# link_b.net
KiCad netlist of a schematic drawn in Altium Designer
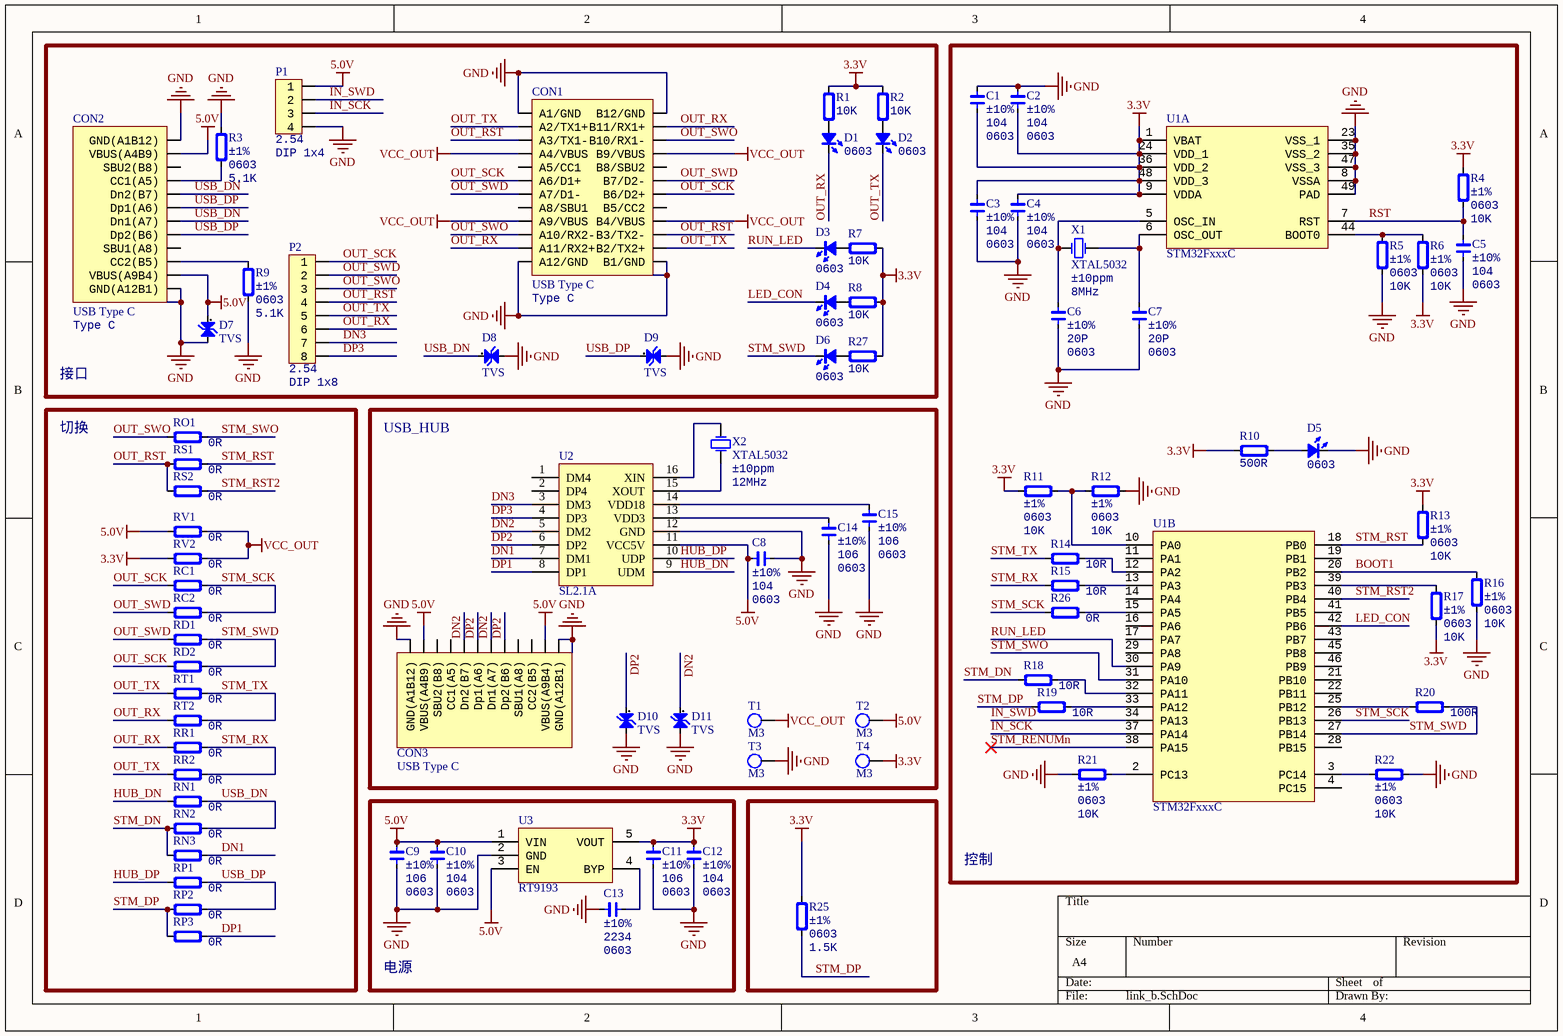
[diagram p0: link_b.SchDoc]

(export (version "E")
  (design (tool "Eeschema 10.0.6"))
  (components
    (comp (ref "C1")
      (value "104")
      (footprint "CAP_0603")
      (description "Capacitor")
      (fields (field (name "NOTE") "±10%") (field (name "TYPE") "0603") (field (name "Comment") "C0603"))
      (libsource (lib "Integrated_Library") (part "Cap_0603"))
    )
    (comp (ref "C2")
      (value "104")
      (footprint "CAP_0603")
      (description "Capacitor")
      (fields (field (name "NOTE") "±10%") (field (name "TYPE") "0603") (field (name "Comment") "C0603"))
      (libsource (lib "Integrated_Library") (part "Cap_0603"))
    )
    (comp (ref "C3")
      (value "104")
      (footprint "CAP_0603")
      (description "Capacitor")
      (fields (field (name "NOTE") "±10%") (field (name "TYPE") "0603") (field (name "Comment") "C0603"))
      (libsource (lib "Integrated_Library") (part "Cap_0603"))
    )
    (comp (ref "C4")
      (value "104")
      (footprint "CAP_0603")
      (description "Capacitor")
      (fields (field (name "NOTE") "±10%") (field (name "TYPE") "0603") (field (name "Comment") "C0603"))
      (libsource (lib "Integrated_Library") (part "Cap_0603"))
    )
    (comp (ref "C5")
      (value "104")
      (footprint "CAP_0603")
      (description "Capacitor")
      (fields (field (name "NOTE") "±10%") (field (name "TYPE") "0603") (field (name "Comment") "C0603"))
      (libsource (lib "Integrated_Library") (part "Cap_0603"))
    )
    (comp (ref "C6")
      (value "20P")
      (footprint "CAP_0603")
      (description "Capacitor")
      (fields (field (name "NOTE") "±10%") (field (name "TYPE") "0603") (field (name "Comment") "C0603"))
      (libsource (lib "Integrated_Library") (part "Cap_0603"))
    )
    (comp (ref "C7")
      (value "20P")
      (footprint "CAP_0603")
      (description "Capacitor")
      (fields (field (name "NOTE") "±10%") (field (name "TYPE") "0603") (field (name "Comment") "C0603"))
      (libsource (lib "Integrated_Library") (part "Cap_0603"))
    )
    (comp (ref "C8")
      (value "104")
      (footprint "CAP_0603")
      (description "Capacitor")
      (fields (field (name "NOTE") "±10%") (field (name "TYPE") "0603") (field (name "Comment") "C0603"))
      (libsource (lib "") (part "Cap_0603_3"))
    )
    (comp (ref "C9")
      (value "106")
      (footprint "CAP_0603")
      (description "Capacitor")
      (fields (field (name "NOTE") "±10%") (field (name "TYPE") "0603") (field (name "Comment") "C0603"))
      (libsource (lib "Integrated_Library") (part "Cap_0603"))
    )
    (comp (ref "C10")
      (value "104")
      (footprint "CAP_0603")
      (description "Capacitor")
      (fields (field (name "NOTE") "±10%") (field (name "TYPE") "0603") (field (name "Comment") "C0603"))
      (libsource (lib "Integrated_Library") (part "Cap_0603"))
    )
    (comp (ref "C11")
      (value "106")
      (footprint "CAP_0603")
      (description "Capacitor")
      (fields (field (name "NOTE") "±10%") (field (name "TYPE") "0603") (field (name "Comment") "C0603"))
      (libsource (lib "Integrated_Library") (part "Cap_0603"))
    )
    (comp (ref "C12")
      (value "104")
      (footprint "CAP_0603")
      (description "Capacitor")
      (fields (field (name "NOTE") "±10%") (field (name "TYPE") "0603") (field (name "Comment") "C0603"))
      (libsource (lib "Integrated_Library") (part "Cap_0603"))
    )
    (comp (ref "C13")
      (value "2234")
      (footprint "CAP_0603")
      (description "Capacitor")
      (fields (field (name "NOTE") "±10%") (field (name "TYPE") "0603") (field (name "Comment") "C0603"))
      (libsource (lib "") (part "Cap_0603_1"))
    )
    (comp (ref "C14")
      (value "106")
      (footprint "CAP_0603")
      (description "Capacitor")
      (fields (field (name "NOTE") "±10%") (field (name "TYPE") "0603") (field (name "Comment") "C0603"))
      (libsource (lib "") (part "Cap_0603_2"))
    )
    (comp (ref "C15")
      (value "106")
      (footprint "CAP_0603")
      (description "Capacitor")
      (fields (field (name "NOTE") "±10%") (field (name "TYPE") "0603") (field (name "Comment") "C0603"))
      (libsource (lib "") (part "Cap_0603_2"))
    )
    (comp (ref "CON1")
      (value "USB Type C")
      (footprint "USB_TypeC_SMD_24P")
      (description "USB")
      (fields (field (name "ALTIUM_VALUE") "Type C"))
      (libsource (lib "Integrated_Library") (part "USB_TypeC"))
    )
    (comp (ref "CON2")
      (value "USB Type C")
      (footprint "USB_TypeC_SMD_16P")
      (description "USB")
      (fields (field (name "ALTIUM_VALUE") "Type C"))
      (libsource (lib "") (part "USB_TypeC_16P_1"))
    )
    (comp (ref "CON3")
      (value "USB Type C")
      (footprint "USB_TypeC_SMD_16P")
      (description "USB")
      (libsource (lib "Integrated_Library") (part "USB_TypeC_16P"))
    )
    (comp (ref "D1")
      (value "D0603")
      (footprint "LED_0603_RED")
      (description "LED")
      (fields (field (name "TYPE") "0603"))
      (libsource (lib "") (part "LED_0603_1"))
    )
    (comp (ref "D2")
      (value "D0603")
      (footprint "LED_0603_RED")
      (description "LED")
      (fields (field (name "TYPE") "0603"))
      (libsource (lib "") (part "LED_0603_1"))
    )
    (comp (ref "D3")
      (value "D0603")
      (footprint "LED_0603_RED")
      (description "LED")
      (fields (field (name "TYPE") "0603"))
      (libsource (lib "Integrated_Library") (part "LED_0603"))
    )
    (comp (ref "D4")
      (value "D0603")
      (footprint "LED_0603_RED")
      (description "LED")
      (fields (field (name "TYPE") "0603"))
      (libsource (lib "Integrated_Library") (part "LED_0603"))
    )
    (comp (ref "D5")
      (value "D0603")
      (footprint "LED_0603_RED")
      (description "LED")
      (fields (field (name "TYPE") "0603"))
      (libsource (lib "") (part "LED_0603_2"))
    )
    (comp (ref "D6")
      (value "D0603")
      (footprint "LED_0603_RED")
      (description "LED")
      (fields (field (name "TYPE") "0603"))
      (libsource (lib "Integrated_Library") (part "LED_0603"))
    )
    (comp (ref "D7")
      (value "TVS")
      (footprint "LED_0603_YELLOW")
      (description "静电保护二极管,VRWM=5V.IPP=9.4A")
      (libsource (lib "MxM_Library") (part "ESD LESD5D5.0CT1G"))
    )
    (comp (ref "D8")
      (value "TVS")
      (footprint "LED_0603_YELLOW")
      (description "静电保护二极管,VRWM=5V.IPP=9.4A")
      (libsource (lib "MxM_Library") (part "ESD LESD5D5.0CT1G"))
    )
    (comp (ref "D9")
      (value "TVS")
      (footprint "LED_0603_YELLOW")
      (description "静电保护二极管,VRWM=5V.IPP=9.4A")
      (libsource (lib "MxM_Library") (part "ESD LESD5D5.0CT1G"))
    )
    (comp (ref "D10")
      (value "TVS")
      (footprint "LED_0603_YELLOW")
      (description "静电保护二极管,VRWM=5V.IPP=9.4A")
      (libsource (lib "MxM_Library") (part "ESD LESD5D5.0CT1G"))
    )
    (comp (ref "D11")
      (value "TVS")
      (footprint "LED_0603_YELLOW")
      (description "静电保护二极管,VRWM=5V.IPP=9.4A")
      (libsource (lib "MxM_Library") (part "ESD LESD5D5.0CT1G"))
    )
    (comp (ref "P1")
      (value "2.54")
      (footprint "HDR1x4_TOP")
      (description "Header Top")
      (fields (field (name "TYPE") "DIP 1x4") (field (name "Comment") "HDR1x4"))
      (libsource (lib "Integrated_Library") (part "HDR1x4_2.54TOP"))
    )
    (comp (ref "P2")
      (value "2.54")
      (footprint "HDR1x8_TOP")
      (description "Header Top")
      (fields (field (name "TYPE") "DIP 1x8") (field (name "Comment") "HDR1x8"))
      (libsource (lib "Integrated_Library") (part "HDR1x8_2.54TOP"))
    )
    (comp (ref "R1")
      (value "10K")
      (footprint "RES_0603")
      (description "Resistor")
      (fields (field (name "Comment") "R0603"))
      (libsource (lib "Integrated_Library") (part "Res_0603"))
    )
    (comp (ref "R2")
      (value "10K")
      (footprint "RES_0603")
      (description "Resistor")
      (fields (field (name "Comment") "R0603"))
      (libsource (lib "Integrated_Library") (part "Res_0603"))
    )
    (comp (ref "R3")
      (value "5.1K")
      (footprint "RES_0603")
      (description "Resistor")
      (fields (field (name "NOTE") "±1%") (field (name "TYPE") "0603") (field (name "Comment") "R0603"))
      (libsource (lib "Integrated_Library") (part "Res_0603"))
    )
    (comp (ref "R4")
      (value "10K")
      (footprint "RES_0603")
      (description "Resistor")
      (fields (field (name "NOTE") "±1%") (field (name "TYPE") "0603") (field (name "Comment") "R0603"))
      (libsource (lib "Integrated_Library") (part "Res_0603"))
    )
    (comp (ref "R5")
      (value "10K")
      (footprint "RES_0603")
      (description "Resistor")
      (fields (field (name "NOTE") "±1%") (field (name "TYPE") "0603") (field (name "Comment") "R0603"))
      (libsource (lib "Integrated_Library") (part "Res_0603"))
    )
    (comp (ref "R6")
      (value "10K")
      (footprint "RES_0603")
      (description "Resistor")
      (fields (field (name "NOTE") "±1%") (field (name "TYPE") "0603") (field (name "Comment") "R0603"))
      (libsource (lib "Integrated_Library") (part "Res_0603"))
    )
    (comp (ref "R7")
      (value "10K")
      (footprint "RES_0603")
      (description "Resistor")
      (fields (field (name "Comment") "R0603"))
      (libsource (lib "Integrated_Library") (part "Res_0603"))
    )
    (comp (ref "R8")
      (value "10K")
      (footprint "RES_0603")
      (description "Resistor")
      (fields (field (name "Comment") "R0603"))
      (libsource (lib "Integrated_Library") (part "Res_0603"))
    )
    (comp (ref "R9")
      (value "5.1K")
      (footprint "RES_0603")
      (description "Resistor")
      (fields (field (name "NOTE") "±1%") (field (name "TYPE") "0603") (field (name "Comment") "R0603"))
      (libsource (lib "Integrated_Library") (part "Res_0603"))
    )
    (comp (ref "R10")
      (value "500R")
      (footprint "RES_0603")
      (description "Resistor")
      (fields (field (name "Comment") "R0603"))
      (libsource (lib "Integrated_Library") (part "Res_0603"))
    )
    (comp (ref "R11")
      (value "10K")
      (footprint "RES_0603")
      (description "Resistor")
      (fields (field (name "NOTE") "±1%") (field (name "TYPE") "0603") (field (name "Comment") "R0603"))
      (libsource (lib "Integrated_Library") (part "Res_0603"))
    )
    (comp (ref "R12")
      (value "10K")
      (footprint "RES_0603")
      (description "Resistor")
      (fields (field (name "NOTE") "±1%") (field (name "TYPE") "0603") (field (name "Comment") "R0603"))
      (libsource (lib "Integrated_Library") (part "Res_0603"))
    )
    (comp (ref "R13")
      (value "10K")
      (footprint "RES_0603")
      (description "Resistor")
      (fields (field (name "NOTE") "±1%") (field (name "TYPE") "0603") (field (name "Comment") "R0603"))
      (libsource (lib "Integrated_Library") (part "Res_0603"))
    )
    (comp (ref "R14")
      (value "10R")
      (footprint "RES_0603")
      (description "Resistor")
      (fields (field (name "Comment") "R0603"))
      (libsource (lib "Integrated_Library") (part "Res_0603"))
    )
    (comp (ref "R15")
      (value "10R")
      (footprint "RES_0603")
      (description "Resistor")
      (fields (field (name "Comment") "R0603"))
      (libsource (lib "Integrated_Library") (part "Res_0603"))
    )
    (comp (ref "R16")
      (value "10K")
      (footprint "RES_0603")
      (description "Resistor")
      (fields (field (name "NOTE") "±1%") (field (name "TYPE") "0603") (field (name "Comment") "R0603"))
      (libsource (lib "Integrated_Library") (part "Res_0603"))
    )
    (comp (ref "R17")
      (value "10K")
      (footprint "RES_0603")
      (description "Resistor")
      (fields (field (name "NOTE") "±1%") (field (name "TYPE") "0603") (field (name "Comment") "R0603"))
      (libsource (lib "Integrated_Library") (part "Res_0603"))
    )
    (comp (ref "R18")
      (value "10R")
      (footprint "RES_0603")
      (description "Resistor")
      (fields (field (name "Comment") "R0603"))
      (libsource (lib "Integrated_Library") (part "Res_0603"))
    )
    (comp (ref "R19")
      (value "10R")
      (footprint "RES_0603")
      (description "Resistor")
      (fields (field (name "Comment") "R0603"))
      (libsource (lib "Integrated_Library") (part "Res_0603"))
    )
    (comp (ref "R20")
      (value "100R")
      (footprint "RES_0603")
      (description "Resistor")
      (fields (field (name "Comment") "R0603"))
      (libsource (lib "Integrated_Library") (part "Res_0603"))
    )
    (comp (ref "R21")
      (value "10K")
      (footprint "RES_0603")
      (description "Resistor")
      (fields (field (name "NOTE") "±1%") (field (name "TYPE") "0603") (field (name "Comment") "R0603"))
      (libsource (lib "Integrated_Library") (part "Res_0603"))
    )
    (comp (ref "R22")
      (value "10K")
      (footprint "RES_0603")
      (description "Resistor")
      (fields (field (name "NOTE") "±1%") (field (name "TYPE") "0603") (field (name "Comment") "R0603"))
      (libsource (lib "Integrated_Library") (part "Res_0603"))
    )
    (comp (ref "R25")
      (value "1.5K")
      (footprint "RES_0603")
      (description "Resistor")
      (fields (field (name "NOTE") "±1%") (field (name "TYPE") "0603") (field (name "Comment") "R0603"))
      (libsource (lib "Integrated_Library") (part "Res_0603"))
    )
    (comp (ref "R26")
      (value "0R")
      (footprint "RES_0603")
      (description "Resistor")
      (fields (field (name "Comment") "R0603"))
      (libsource (lib "Integrated_Library") (part "Res_0603"))
    )
    (comp (ref "R27")
      (value "10K")
      (footprint "RES_0603")
      (description "Resistor")
      (fields (field (name "Comment") "R0603"))
      (libsource (lib "Integrated_Library") (part "Res_0603"))
    )
    (comp (ref "RC1")
      (value "0R")
      (footprint "RES_0603")
      (description "Resistor")
      (fields (field (name "Comment") "R0603"))
      (libsource (lib "Integrated_Library") (part "Res_0603"))
    )
    (comp (ref "RC2")
      (value "0R")
      (footprint "RES_0603")
      (description "Resistor")
      (fields (field (name "Comment") "R0603"))
      (libsource (lib "Integrated_Library") (part "Res_0603"))
    )
    (comp (ref "RD1")
      (value "0R")
      (footprint "RES_0603")
      (description "Resistor")
      (fields (field (name "Comment") "R0603"))
      (libsource (lib "Integrated_Library") (part "Res_0603"))
    )
    (comp (ref "RD2")
      (value "0R")
      (footprint "RES_0603")
      (description "Resistor")
      (fields (field (name "Comment") "R0603"))
      (libsource (lib "Integrated_Library") (part "Res_0603"))
    )
    (comp (ref "RN1")
      (value "0R")
      (footprint "RES_0603")
      (description "Resistor")
      (fields (field (name "Comment") "R0603"))
      (libsource (lib "Integrated_Library") (part "Res_0603"))
    )
    (comp (ref "RN2")
      (value "0R")
      (footprint "RES_0603")
      (description "Resistor")
      (fields (field (name "Comment") "R0603"))
      (libsource (lib "Integrated_Library") (part "Res_0603"))
    )
    (comp (ref "RN3")
      (value "0R")
      (footprint "RES_0603")
      (description "Resistor")
      (fields (field (name "Comment") "R0603"))
      (libsource (lib "Integrated_Library") (part "Res_0603"))
    )
    (comp (ref "RO1")
      (value "0R")
      (footprint "RES_0603")
      (description "Resistor")
      (fields (field (name "Comment") "R0603"))
      (libsource (lib "Integrated_Library") (part "Res_0603"))
    )
    (comp (ref "RP1")
      (value "0R")
      (footprint "RES_0603")
      (description "Resistor")
      (fields (field (name "Comment") "R0603"))
      (libsource (lib "Integrated_Library") (part "Res_0603"))
    )
    (comp (ref "RP2")
      (value "0R")
      (footprint "RES_0603")
      (description "Resistor")
      (fields (field (name "Comment") "R0603"))
      (libsource (lib "Integrated_Library") (part "Res_0603"))
    )
    (comp (ref "RP3")
      (value "0R")
      (footprint "RES_0603")
      (description "Resistor")
      (fields (field (name "Comment") "R0603"))
      (libsource (lib "Integrated_Library") (part "Res_0603"))
    )
    (comp (ref "RR1")
      (value "0R")
      (footprint "RES_0603")
      (description "Resistor")
      (fields (field (name "Comment") "R0603"))
      (libsource (lib "Integrated_Library") (part "Res_0603"))
    )
    (comp (ref "RR2")
      (value "0R")
      (footprint "RES_0603")
      (description "Resistor")
      (fields (field (name "Comment") "R0603"))
      (libsource (lib "Integrated_Library") (part "Res_0603"))
    )
    (comp (ref "RS1")
      (value "0R")
      (footprint "RES_0603")
      (description "Resistor")
      (fields (field (name "Comment") "R0603"))
      (libsource (lib "Integrated_Library") (part "Res_0603"))
    )
    (comp (ref "RS2")
      (value "0R")
      (footprint "RES_0603")
      (description "Resistor")
      (fields (field (name "Comment") "R0603"))
      (libsource (lib "Integrated_Library") (part "Res_0603"))
    )
    (comp (ref "RT1")
      (value "0R")
      (footprint "RES_0603")
      (description "Resistor")
      (fields (field (name "Comment") "R0603"))
      (libsource (lib "Integrated_Library") (part "Res_0603"))
    )
    (comp (ref "RT2")
      (value "0R")
      (footprint "RES_0603")
      (description "Resistor")
      (fields (field (name "Comment") "R0603"))
      (libsource (lib "Integrated_Library") (part "Res_0603"))
    )
    (comp (ref "RV1")
      (value "0R")
      (footprint "RES_0603")
      (description "Resistor")
      (fields (field (name "Comment") "R0603"))
      (libsource (lib "Integrated_Library") (part "Res_0603"))
    )
    (comp (ref "RV2")
      (value "0R")
      (footprint "RES_0603")
      (description "Resistor")
      (fields (field (name "Comment") "R0603"))
      (libsource (lib "Integrated_Library") (part "Res_0603"))
    )
    (comp (ref "T1")
      (value "M3")
      (footprint "M3")
      (description "M3 Nut")
      (libsource (lib "Integrated_Library") (part "M3"))
    )
    (comp (ref "T2")
      (value "M3")
      (footprint "M3")
      (description "M3 Nut")
      (libsource (lib "Integrated_Library") (part "M3"))
    )
    (comp (ref "T3")
      (value "M3")
      (footprint "M3")
      (description "M3 Nut")
      (libsource (lib "Integrated_Library") (part "M3"))
    )
    (comp (ref "T4")
      (value "M3")
      (footprint "M3")
      (description "M3 Nut")
      (libsource (lib "Integrated_Library") (part "M3"))
    )
    (comp (ref "U1")
      (value "STM32FxxxC")
      (footprint "LQFP_QNF_48")
      (description "MCU ST")
      (fields (field (name "MANUFACTURER") "STMicroelectronics"))
      (libsource (lib "Integrated_Library") (part "STM32FxxxC"))
    )
    (comp (ref "U2")
      (value "SL2.1A")
      (footprint "SOP16")
      (description "USB HUB")
      (libsource (lib "Integrated_Library") (part "SL2.1A"))
    )
    (comp (ref "U3")
      (value "RT9193")
      (footprint "SOT23-5")
      (description "Power")
      (libsource (lib "Integrated_Library") (part "RT9193"))
    )
    (comp (ref "X1")
      (value "XTAL5032")
      (footprint "XT_5032_2")
      (description "Crystal Oscillator")
      (fields (field (name "SPECIFICATION") "±10ppm") (field (name "ALTIUM_VALUE") "8MHz"))
      (libsource (lib "Integrated_Library") (part "XTAL_5032_2P"))
    )
    (comp (ref "X2")
      (value "XTAL5032")
      (footprint "XT_5032_2")
      (description "Crystal Oscillator")
      (fields (field (name "SPECIFICATION") "±10ppm") (field (name "ALTIUM_VALUE") "12MHz"))
      (libsource (lib "Integrated_Library") (part "XTAL_5032_2P"))
    )
  )
  (nets
    (net (code "1") (name "/BOOT1") (class "Default")
      (node (ref "R16") (pin "1") (pinfunction "1_1") (pintype "passive"))
      (node (ref "U1") (pin "20") (pinfunction "PB2_20") (pintype "passive"))
    )
    (net (code "2") (name "/DN1") (class "Default")
      (node (ref "RN3") (pin "1") (pinfunction "1_1") (pintype "passive"))
      (node (ref "U2") (pin "7") (pinfunction "DM1_7") (pintype "passive"))
    )
    (net (code "3") (name "/DN2") (class "Default")
      (node (ref "CON3") (pin "A7") (pinfunction "Dn1(A7)_A7") (pintype "passive"))
      (node (ref "CON3") (pin "B7") (pinfunction "Dn2(B7)_B7") (pintype "passive"))
      (node (ref "D11") (pin "1") (pinfunction "A_1") (pintype "passive"))
      (node (ref "U2") (pin "5") (pinfunction "DM2_5") (pintype "passive"))
    )
    (net (code "4") (name "/DN3") (class "Default")
      (node (ref "P2") (pin "7") (pinfunction "7_7") (pintype "passive"))
      (node (ref "U2") (pin "3") (pinfunction "DM3_3") (pintype "passive"))
    )
    (net (code "5") (name "/DP1") (class "Default")
      (node (ref "RP3") (pin "1") (pinfunction "1_1") (pintype "passive"))
      (node (ref "U2") (pin "8") (pinfunction "DP1_8") (pintype "passive"))
    )
    (net (code "6") (name "/DP2") (class "Default")
      (node (ref "CON3") (pin "A6") (pinfunction "Dp1(A6)_A6") (pintype "passive"))
      (node (ref "CON3") (pin "B6") (pinfunction "Dp2(B6)_B6") (pintype "passive"))
      (node (ref "D10") (pin "1") (pinfunction "A_1") (pintype "passive"))
      (node (ref "U2") (pin "6") (pinfunction "DP2_6") (pintype "passive"))
    )
    (net (code "7") (name "/DP3") (class "Default")
      (node (ref "P2") (pin "8") (pinfunction "8_8") (pintype "passive"))
      (node (ref "U2") (pin "4") (pinfunction "DP3_4") (pintype "passive"))
    )
    (net (code "8") (name "/HUB_DN") (class "Default")
      (node (ref "RN1") (pin "2") (pinfunction "2_2") (pintype "passive"))
      (node (ref "U2") (pin "9") (pinfunction "UDM_9") (pintype "passive"))
    )
    (net (code "9") (name "/HUB_DP") (class "Default")
      (node (ref "RP1") (pin "2") (pinfunction "2_2") (pintype "passive"))
      (node (ref "U2") (pin "10") (pinfunction "UDP_10") (pintype "passive"))
    )
    (net (code "10") (name "/IN_SCK") (class "Default")
      (node (ref "P1") (pin "3") (pinfunction "3_3") (pintype "passive"))
      (node (ref "U1") (pin "37") (pinfunction "PA14_37") (pintype "passive"))
    )
    (net (code "11") (name "/IN_SWD") (class "Default")
      (node (ref "P1") (pin "2") (pinfunction "2_2") (pintype "passive"))
      (node (ref "U1") (pin "34") (pinfunction "PA13_34") (pintype "passive"))
    )
    (net (code "12") (name "/LED_CON") (class "Default")
      (node (ref "D4") (pin "2") (pinfunction "K_2") (pintype "passive"))
      (node (ref "U1") (pin "42") (pinfunction "PB6_42") (pintype "passive"))
    )
    (net (code "13") (name "/OUT_RST") (class "Default")
      (node (ref "CON1") (pin "A3") (pinfunction "A3/TX1-_A3") (pintype "passive"))
      (node (ref "CON1") (pin "B3") (pinfunction "B3/TX2-_B3") (pintype "passive"))
      (node (ref "P2") (pin "4") (pinfunction "4_4") (pintype "passive"))
      (node (ref "RS1") (pin "2") (pinfunction "2_2") (pintype "passive"))
      (node (ref "RS2") (pin "2") (pinfunction "2_2") (pintype "passive"))
    )
    (net (code "14") (name "/OUT_RX") (class "Default")
      (node (ref "CON1") (pin "A11") (pinfunction "A11/RX2+_A11") (pintype "passive"))
      (node (ref "CON1") (pin "B11") (pinfunction "B11/RX1+_B11") (pintype "passive"))
      (node (ref "D1") (pin "2") (pinfunction "K_2") (pintype "passive"))
      (node (ref "P2") (pin "6") (pinfunction "6_6") (pintype "passive"))
      (node (ref "RR1") (pin "2") (pinfunction "2_2") (pintype "passive"))
      (node (ref "RT2") (pin "2") (pinfunction "2_2") (pintype "passive"))
    )
    (net (code "15") (name "/OUT_SCK") (class "Default")
      (node (ref "CON1") (pin "A6") (pinfunction "A6/D1+_A6") (pintype "passive"))
      (node (ref "CON1") (pin "B6") (pinfunction "B6/D2+_B6") (pintype "passive"))
      (node (ref "P2") (pin "1") (pinfunction "1_1") (pintype "passive"))
      (node (ref "RC1") (pin "2") (pinfunction "2_2") (pintype "passive"))
      (node (ref "RD2") (pin "2") (pinfunction "2_2") (pintype "passive"))
    )
    (net (code "16") (name "/OUT_SWD") (class "Default")
      (node (ref "CON1") (pin "A7") (pinfunction "A7/D1-_A7") (pintype "passive"))
      (node (ref "CON1") (pin "B7") (pinfunction "B7/D2-_B7") (pintype "passive"))
      (node (ref "P2") (pin "2") (pinfunction "2_2") (pintype "passive"))
      (node (ref "RC2") (pin "2") (pinfunction "2_2") (pintype "passive"))
      (node (ref "RD1") (pin "2") (pinfunction "2_2") (pintype "passive"))
    )
    (net (code "17") (name "/OUT_SWO") (class "Default")
      (node (ref "CON1") (pin "A10") (pinfunction "A10/RX2-_A10") (pintype "passive"))
      (node (ref "CON1") (pin "B10") (pinfunction "B10/RX1-_B10") (pintype "passive"))
      (node (ref "P2") (pin "3") (pinfunction "3_3") (pintype "passive"))
      (node (ref "RO1") (pin "2") (pinfunction "2_2") (pintype "passive"))
    )
    (net (code "18") (name "/OUT_TX") (class "Default")
      (node (ref "CON1") (pin "A2") (pinfunction "A2/TX1+_A2") (pintype "passive"))
      (node (ref "CON1") (pin "B2") (pinfunction "B2/TX2+_B2") (pintype "passive"))
      (node (ref "D2") (pin "2") (pinfunction "K_2") (pintype "passive"))
      (node (ref "P2") (pin "5") (pinfunction "5_5") (pintype "passive"))
      (node (ref "RR2") (pin "2") (pinfunction "2_2") (pintype "passive"))
      (node (ref "RT1") (pin "2") (pinfunction "2_2") (pintype "passive"))
    )
    (net (code "19") (name "/RST") (class "Default")
      (node (ref "C5") (pin "2") (pinfunction "2_2") (pintype "passive"))
      (node (ref "R4") (pin "1") (pinfunction "1_1") (pintype "passive"))
      (node (ref "U1") (pin "7") (pinfunction "RST_7") (pintype "passive"))
    )
    (net (code "20") (name "/RUN_LED") (class "Default")
      (node (ref "D3") (pin "2") (pinfunction "K_2") (pintype "passive"))
      (node (ref "U1") (pin "30") (pinfunction "PA9_30") (pintype "passive"))
    )
    (net (code "21") (name "/STM_DN") (class "Default")
      (node (ref "R18") (pin "2") (pinfunction "2_2") (pintype "passive"))
      (node (ref "RN2") (pin "2") (pinfunction "2_2") (pintype "passive"))
      (node (ref "RN3") (pin "2") (pinfunction "2_2") (pintype "passive"))
    )
    (net (code "22") (name "/STM_DP") (class "Default")
      (node (ref "R19") (pin "2") (pinfunction "2_2") (pintype "passive"))
      (node (ref "R25") (pin "1") (pinfunction "1_1") (pintype "passive"))
      (node (ref "RP2") (pin "2") (pinfunction "2_2") (pintype "passive"))
      (node (ref "RP3") (pin "2") (pinfunction "2_2") (pintype "passive"))
    )
    (net (code "23") (name "/STM_RENUMn") (class "Default")
      (node (ref "U1") (pin "38") (pinfunction "PA15_38") (pintype "passive+no_connect"))
    )
    (net (code "24") (name "/STM_RST") (class "Default")
      (node (ref "R13") (pin "1") (pinfunction "1_1") (pintype "passive"))
      (node (ref "RS1") (pin "1") (pinfunction "1_1") (pintype "passive"))
      (node (ref "U1") (pin "18") (pinfunction "PB0_18") (pintype "passive"))
    )
    (net (code "25") (name "/STM_RST2") (class "Default")
      (node (ref "RS2") (pin "1") (pinfunction "1_1") (pintype "passive"))
      (node (ref "U1") (pin "40") (pinfunction "PB4_40") (pintype "passive"))
    )
    (net (code "26") (name "/STM_RX") (class "Default")
      (node (ref "R15") (pin "2") (pinfunction "2_2") (pintype "passive"))
      (node (ref "RR1") (pin "1") (pinfunction "1_1") (pintype "passive"))
      (node (ref "RR2") (pin "1") (pinfunction "1_1") (pintype "passive"))
    )
    (net (code "27") (name "/STM_SCK") (class "Default")
      (node (ref "R26") (pin "2") (pinfunction "2_2") (pintype "passive"))
      (node (ref "RC1") (pin "1") (pinfunction "1_1") (pintype "passive"))
      (node (ref "RC2") (pin "1") (pinfunction "1_1") (pintype "passive"))
      (node (ref "U1") (pin "26") (pinfunction "PB13_26") (pintype "passive"))
    )
    (net (code "28") (name "/STM_SWD") (class "Default")
      (node (ref "D6") (pin "2") (pinfunction "K_2") (pintype "passive"))
      (node (ref "R20") (pin "1") (pinfunction "1_1") (pintype "passive"))
      (node (ref "RD1") (pin "1") (pinfunction "1_1") (pintype "passive"))
      (node (ref "RD2") (pin "1") (pinfunction "1_1") (pintype "passive"))
      (node (ref "U1") (pin "27") (pinfunction "PB14_27") (pintype "passive"))
    )
    (net (code "29") (name "/STM_SWO") (class "Default")
      (node (ref "RO1") (pin "1") (pinfunction "1_1") (pintype "passive"))
      (node (ref "U1") (pin "31") (pinfunction "PA10_31") (pintype "passive"))
    )
    (net (code "30") (name "/STM_TX") (class "Default")
      (node (ref "R14") (pin "2") (pinfunction "2_2") (pintype "passive"))
      (node (ref "RT1") (pin "1") (pinfunction "1_1") (pintype "passive"))
      (node (ref "RT2") (pin "1") (pinfunction "1_1") (pintype "passive"))
    )
    (net (code "31") (name "/USB_DN") (class "Default")
      (node (ref "CON2") (pin "A7") (pinfunction "Dn1(A7)_A7") (pintype "passive"))
      (node (ref "CON2") (pin "B7") (pinfunction "Dn2(B7)_B7") (pintype "passive"))
      (node (ref "D8") (pin "1") (pinfunction "A_1") (pintype "passive"))
      (node (ref "RN1") (pin "1") (pinfunction "1_1") (pintype "passive"))
      (node (ref "RN2") (pin "1") (pinfunction "1_1") (pintype "passive"))
    )
    (net (code "32") (name "/USB_DP") (class "Default")
      (node (ref "CON2") (pin "A6") (pinfunction "Dp1(A6)_A6") (pintype "passive"))
      (node (ref "CON2") (pin "B6") (pinfunction "Dp2(B6)_B6") (pintype "passive"))
      (node (ref "D9") (pin "1") (pinfunction "A_1") (pintype "passive"))
      (node (ref "RP1") (pin "1") (pinfunction "1_1") (pintype "passive"))
      (node (ref "RP2") (pin "1") (pinfunction "1_1") (pintype "passive"))
    )
    (net (code "33") (name "3.3V") (class "Default")
      (node (ref "C1") (pin "1") (pinfunction "1_1") (pintype "passive"))
      (node (ref "C11") (pin "2") (pinfunction "2_2") (pintype "passive"))
      (node (ref "C12") (pin "2") (pinfunction "2_2") (pintype "passive"))
      (node (ref "C2") (pin "1") (pinfunction "1_1") (pintype "passive"))
      (node (ref "C3") (pin "2") (pinfunction "2_2") (pintype "passive"))
      (node (ref "C4") (pin "2") (pinfunction "2_2") (pintype "passive"))
      (node (ref "R1") (pin "1") (pinfunction "1_1") (pintype "passive"))
      (node (ref "R10") (pin "1") (pinfunction "1_1") (pintype "passive"))
      (node (ref "R11") (pin "2") (pinfunction "2_2") (pintype "passive"))
      (node (ref "R13") (pin "2") (pinfunction "2_2") (pintype "passive"))
      (node (ref "R17") (pin "2") (pinfunction "2_2") (pintype "passive"))
      (node (ref "R2") (pin "1") (pinfunction "1_1") (pintype "passive"))
      (node (ref "R25") (pin "2") (pinfunction "2_2") (pintype "passive"))
      (node (ref "R27") (pin "1") (pinfunction "1_1") (pintype "passive"))
      (node (ref "R4") (pin "2") (pinfunction "2_2") (pintype "passive"))
      (node (ref "R6") (pin "1") (pinfunction "1_1") (pintype "passive"))
      (node (ref "R7") (pin "1") (pinfunction "1_1") (pintype "passive"))
      (node (ref "R8") (pin "1") (pinfunction "1_1") (pintype "passive"))
      (node (ref "RV2") (pin "2") (pinfunction "2_2") (pintype "passive"))
      (node (ref "T4") (pin "1") (pinfunction "1_1") (pintype "passive"))
      (node (ref "U1") (pin "1") (pinfunction "VBAT_1") (pintype "passive"))
      (node (ref "U1") (pin "24") (pinfunction "VDD_1_24") (pintype "passive"))
      (node (ref "U1") (pin "36") (pinfunction "VDD_2_36") (pintype "passive"))
      (node (ref "U1") (pin "48") (pinfunction "VDD_3_48") (pintype "passive"))
      (node (ref "U1") (pin "9") (pinfunction "VDDA_9") (pintype "passive"))
      (node (ref "U3") (pin "5") (pinfunction "VOUT_5") (pintype "passive"))
    )
    (net (code "34") (name "5.0V") (class "Default")
      (node (ref "C10") (pin "2") (pinfunction "2_2") (pintype "passive"))
      (node (ref "C8") (pin "2") (pinfunction "2_2") (pintype "passive"))
      (node (ref "C9") (pin "2") (pinfunction "2_2") (pintype "passive"))
      (node (ref "CON2") (pin "A4B9") (pinfunction "VBUS(A4B9)_A4B9") (pintype "passive"))
      (node (ref "CON2") (pin "A9B4") (pinfunction "VBUS(A9B4)_A9B4") (pintype "passive"))
      (node (ref "CON3") (pin "A4B9") (pinfunction "VBUS(A4B9)_A4B9") (pintype "passive"))
      (node (ref "CON3") (pin "A9B4") (pinfunction "VBUS(A9B4)_A9B4") (pintype "passive"))
      (node (ref "D7") (pin "1") (pinfunction "A_1") (pintype "passive"))
      (node (ref "P1") (pin "1") (pinfunction "1_1") (pintype "passive"))
      (node (ref "RV1") (pin "2") (pinfunction "2_2") (pintype "passive"))
      (node (ref "T2") (pin "1") (pinfunction "1_1") (pintype "passive"))
      (node (ref "U2") (pin "11") (pinfunction "VCC5V_11") (pintype "passive"))
      (node (ref "U3") (pin "1") (pinfunction "VIN_1") (pintype "passive"))
      (node (ref "U3") (pin "3") (pinfunction "EN_3") (pintype "power_in"))
    )
    (net (code "35") (name "GND") (class "Default")
      (node (ref "C1") (pin "2") (pinfunction "2_2") (pintype "passive"))
      (node (ref "C10") (pin "1") (pinfunction "1_1") (pintype "passive"))
      (node (ref "C11") (pin "1") (pinfunction "1_1") (pintype "passive"))
      (node (ref "C12") (pin "1") (pinfunction "1_1") (pintype "passive"))
      (node (ref "C13") (pin "1") (pinfunction "1_1") (pintype "passive"))
      (node (ref "C14") (pin "2") (pinfunction "2_2") (pintype "passive"))
      (node (ref "C15") (pin "2") (pinfunction "2_2") (pintype "passive"))
      (node (ref "C2") (pin "2") (pinfunction "2_2") (pintype "passive"))
      (node (ref "C3") (pin "1") (pinfunction "1_1") (pintype "passive"))
      (node (ref "C4") (pin "1") (pinfunction "1_1") (pintype "passive"))
      (node (ref "C5") (pin "1") (pinfunction "1_1") (pintype "passive"))
      (node (ref "C6") (pin "1") (pinfunction "1_1") (pintype "passive"))
      (node (ref "C7") (pin "1") (pinfunction "1_1") (pintype "passive"))
      (node (ref "C8") (pin "1") (pinfunction "1_1") (pintype "passive"))
      (node (ref "C9") (pin "1") (pinfunction "1_1") (pintype "passive"))
      (node (ref "CON1") (pin "0") (pinfunction "SH_0") (pintype "passive"))
      (node (ref "CON1") (pin "A1") (pinfunction "A1/GND_A1") (pintype "passive"))
      (node (ref "CON1") (pin "A12") (pinfunction "A12/GND_A12") (pintype "passive"))
      (node (ref "CON1") (pin "B1") (pinfunction "B1/GND_B1") (pintype "passive"))
      (node (ref "CON1") (pin "B12") (pinfunction "B12/GND_B12") (pintype "passive"))
      (node (ref "CON2") (pin "0") (pinfunction "SH_0") (pintype "passive"))
      (node (ref "CON2") (pin "A12B1") (pinfunction "GND(A12B1)_A12B1") (pintype "passive"))
      (node (ref "CON2") (pin "A1B12") (pinfunction "GND(A1B12)_A1B12") (pintype "passive"))
      (node (ref "CON3") (pin "0") (pinfunction "SH_0") (pintype "passive"))
      (node (ref "CON3") (pin "A12B1") (pinfunction "GND(A12B1)_A12B1") (pintype "passive"))
      (node (ref "CON3") (pin "A1B12") (pinfunction "GND(A1B12)_A1B12") (pintype "passive"))
      (node (ref "D10") (pin "2") (pinfunction "K_2") (pintype "passive"))
      (node (ref "D11") (pin "2") (pinfunction "K_2") (pintype "passive"))
      (node (ref "D5") (pin "2") (pinfunction "K_2") (pintype "passive"))
      (node (ref "D7") (pin "2") (pinfunction "K_2") (pintype "passive"))
      (node (ref "D8") (pin "2") (pinfunction "K_2") (pintype "passive"))
      (node (ref "D9") (pin "2") (pinfunction "K_2") (pintype "passive"))
      (node (ref "P1") (pin "4") (pinfunction "4_4") (pintype "passive"))
      (node (ref "R12") (pin "1") (pinfunction "1_1") (pintype "passive"))
      (node (ref "R16") (pin "2") (pinfunction "2_2") (pintype "passive"))
      (node (ref "R21") (pin "1") (pinfunction "1_1") (pintype "passive"))
      (node (ref "R22") (pin "2") (pinfunction "2_2") (pintype "passive"))
      (node (ref "R3") (pin "2") (pinfunction "2_2") (pintype "passive"))
      (node (ref "R5") (pin "1") (pinfunction "1_1") (pintype "passive"))
      (node (ref "R9") (pin "1") (pinfunction "1_1") (pintype "passive"))
      (node (ref "T3") (pin "1") (pinfunction "1_1") (pintype "passive"))
      (node (ref "U1") (pin "23") (pinfunction "VSS_1_23") (pintype "passive"))
      (node (ref "U1") (pin "35") (pinfunction "VSS_2_35") (pintype "passive"))
      (node (ref "U1") (pin "47") (pinfunction "VSS_3_47") (pintype "passive"))
      (node (ref "U1") (pin "49") (pinfunction "PAD_49") (pintype "passive"))
      (node (ref "U1") (pin "8") (pinfunction "VSSA_8") (pintype "passive"))
      (node (ref "U2") (pin "12") (pinfunction "GND_12") (pintype "passive"))
      (node (ref "U3") (pin "2") (pinfunction "GND_2") (pintype "passive"))
    )
    (net (code "36") (name "Net-(CON2-CC1(A5))") (class "Default")
      (node (ref "CON2") (pin "A5") (pinfunction "CC1(A5)_A5") (pintype "passive"))
      (node (ref "R3") (pin "1") (pinfunction "1_1") (pintype "passive"))
    )
    (net (code "37") (name "Net-(CON2-CC2(B5))") (class "Default")
      (node (ref "CON2") (pin "B5") (pinfunction "CC2(B5)_B5") (pintype "passive"))
      (node (ref "R9") (pin "2") (pinfunction "2_2") (pintype "passive"))
    )
    (net (code "38") (name "Net-(D1-A)") (class "Default")
      (node (ref "D1") (pin "1") (pinfunction "A_1") (pintype "passive"))
      (node (ref "R1") (pin "2") (pinfunction "2_2") (pintype "passive"))
    )
    (net (code "39") (name "Net-(D2-A)") (class "Default")
      (node (ref "D2") (pin "1") (pinfunction "A_1") (pintype "passive"))
      (node (ref "R2") (pin "2") (pinfunction "2_2") (pintype "passive"))
    )
    (net (code "40") (name "Net-(D3-A)") (class "Default")
      (node (ref "D3") (pin "1") (pinfunction "A_1") (pintype "passive"))
      (node (ref "R7") (pin "2") (pinfunction "2_2") (pintype "passive"))
    )
    (net (code "41") (name "Net-(D4-A)") (class "Default")
      (node (ref "D4") (pin "1") (pinfunction "A_1") (pintype "passive"))
      (node (ref "R8") (pin "2") (pinfunction "2_2") (pintype "passive"))
    )
    (net (code "42") (name "Net-(D5-A)") (class "Default")
      (node (ref "D5") (pin "1") (pinfunction "A_1") (pintype "passive"))
      (node (ref "R10") (pin "2") (pinfunction "2_2") (pintype "passive"))
    )
    (net (code "43") (name "Net-(D6-A)") (class "Default")
      (node (ref "D6") (pin "1") (pinfunction "A_1") (pintype "passive"))
      (node (ref "R27") (pin "2") (pinfunction "2_2") (pintype "passive"))
    )
    (net (code "44") (name "Net-(U1A-BOOT0)") (class "Default")
      (node (ref "R5") (pin "2") (pinfunction "2_2") (pintype "passive"))
      (node (ref "R6") (pin "2") (pinfunction "2_2") (pintype "passive"))
      (node (ref "U1") (pin "44") (pinfunction "BOOT0_44") (pintype "passive"))
    )
    (net (code "45") (name "Net-(U1A-OSC_IN)") (class "Default")
      (node (ref "C6") (pin "2") (pinfunction "2_2") (pintype "passive"))
      (node (ref "U1") (pin "5") (pinfunction "OSC_IN_5") (pintype "passive"))
      (node (ref "X1") (pin "1") (pinfunction "OSC1_1") (pintype "passive"))
    )
    (net (code "46") (name "Net-(U1A-OSC_OUT)") (class "Default")
      (node (ref "C7") (pin "2") (pinfunction "2_2") (pintype "passive"))
      (node (ref "U1") (pin "6") (pinfunction "OSC_OUT_6") (pintype "passive"))
      (node (ref "X1") (pin "2") (pinfunction "OSC2_2") (pintype "passive"))
    )
    (net (code "47") (name "Net-(U1B-PA0)") (class "Default")
      (node (ref "R11") (pin "1") (pinfunction "1_1") (pintype "passive"))
      (node (ref "R12") (pin "2") (pinfunction "2_2") (pintype "passive"))
      (node (ref "U1") (pin "10") (pinfunction "PA0_10") (pintype "passive"))
    )
    (net (code "48") (name "Net-(U1B-PA2)") (class "Default")
      (node (ref "R14") (pin "1") (pinfunction "1_1") (pintype "passive"))
      (node (ref "U1") (pin "12") (pinfunction "PA2_12") (pintype "passive"))
    )
    (net (code "49") (name "Net-(U1B-PA3)") (class "Default")
      (node (ref "R15") (pin "1") (pinfunction "1_1") (pintype "passive"))
      (node (ref "U1") (pin "13") (pinfunction "PA3_13") (pintype "passive"))
    )
    (net (code "50") (name "Net-(U1B-PA5)") (class "Default")
      (node (ref "R26") (pin "1") (pinfunction "1_1") (pintype "passive"))
      (node (ref "U1") (pin "15") (pinfunction "PA5_15") (pintype "passive"))
    )
    (net (code "51") (name "Net-(U1B-PA11)") (class "Default")
      (node (ref "R18") (pin "1") (pinfunction "1_1") (pintype "passive"))
      (node (ref "U1") (pin "32") (pinfunction "PA11_32") (pintype "passive"))
    )
    (net (code "52") (name "Net-(U1B-PA12)") (class "Default")
      (node (ref "R19") (pin "1") (pinfunction "1_1") (pintype "passive"))
      (node (ref "U1") (pin "33") (pinfunction "PA12_33") (pintype "passive"))
    )
    (net (code "53") (name "Net-(U1B-PB3)") (class "Default")
      (node (ref "R17") (pin "1") (pinfunction "1_1") (pintype "passive"))
      (node (ref "U1") (pin "39") (pinfunction "PB3_39") (pintype "passive"))
    )
    (net (code "54") (name "Net-(U1B-PB12)") (class "Default")
      (node (ref "R20") (pin "2") (pinfunction "2_2") (pintype "passive"))
      (node (ref "U1") (pin "25") (pinfunction "PB12_25") (pintype "passive"))
    )
    (net (code "55") (name "Net-(U1B-PC13)") (class "Default")
      (node (ref "R21") (pin "2") (pinfunction "2_2") (pintype "passive"))
      (node (ref "U1") (pin "2") (pinfunction "PC13_2") (pintype "passive"))
    )
    (net (code "56") (name "Net-(U1B-PC14)") (class "Default")
      (node (ref "R22") (pin "1") (pinfunction "1_1") (pintype "passive"))
      (node (ref "U1") (pin "3") (pinfunction "PC14_3") (pintype "passive"))
    )
    (net (code "57") (name "Net-(U2-VDD3)") (class "Default")
      (node (ref "C14") (pin "1") (pinfunction "1_1") (pintype "passive"))
      (node (ref "U2") (pin "13") (pinfunction "VDD3_13") (pintype "passive"))
    )
    (net (code "58") (name "Net-(U2-VDD18)") (class "Default")
      (node (ref "C15") (pin "1") (pinfunction "1_1") (pintype "passive"))
      (node (ref "U2") (pin "14") (pinfunction "VDD18_14") (pintype "passive"))
    )
    (net (code "59") (name "Net-(U2-XIN)") (class "Default")
      (node (ref "U2") (pin "16") (pinfunction "XIN_16") (pintype "passive"))
      (node (ref "X2") (pin "2") (pinfunction "OSC2_2") (pintype "passive"))
    )
    (net (code "60") (name "Net-(U2-XOUT)") (class "Default")
      (node (ref "U2") (pin "15") (pinfunction "XOUT_15") (pintype "passive"))
      (node (ref "X2") (pin "1") (pinfunction "OSC1_1") (pintype "passive"))
    )
    (net (code "61") (name "Net-(U3-BYP)") (class "Default")
      (node (ref "C13") (pin "2") (pinfunction "2_2") (pintype "passive"))
      (node (ref "U3") (pin "4") (pinfunction "BYP_4") (pintype "passive"))
    )
    (net (code "62") (name "VCC_OUT") (class "Default")
      (node (ref "CON1") (pin "A4") (pinfunction "A4/VBUS_A4") (pintype "passive"))
      (node (ref "CON1") (pin "A9") (pinfunction "A9/VBUS_A9") (pintype "passive"))
      (node (ref "CON1") (pin "B4") (pinfunction "B4/VBUS_B4") (pintype "passive"))
      (node (ref "CON1") (pin "B9") (pinfunction "B9/VBUS_B9") (pintype "passive"))
      (node (ref "RV1") (pin "1") (pinfunction "1_1") (pintype "passive"))
      (node (ref "RV2") (pin "1") (pinfunction "1_1") (pintype "passive"))
      (node (ref "T1") (pin "1") (pinfunction "1_1") (pintype "passive"))
    )
    (net (code "63") (name "unconnected-(CON1-A5{slash}CC1-PadA5)") (class "Default")
      (node (ref "CON1") (pin "A5") (pinfunction "A5/CC1_A5") (pintype "passive"))
    )
    (net (code "64") (name "unconnected-(CON1-A8{slash}SBU1-PadA8)") (class "Default")
      (node (ref "CON1") (pin "A8") (pinfunction "A8/SBU1_A8") (pintype "passive"))
    )
    (net (code "65") (name "unconnected-(CON1-B5{slash}CC2-PadB5)") (class "Default")
      (node (ref "CON1") (pin "B5") (pinfunction "B5/CC2_B5") (pintype "passive"))
    )
    (net (code "66") (name "unconnected-(CON1-B8{slash}SBU2-PadB8)") (class "Default")
      (node (ref "CON1") (pin "B8") (pinfunction "B8/SBU2_B8") (pintype "passive"))
    )
    (net (code "67") (name "unconnected-(CON2-SBU1(A8)-PadA8)") (class "Default")
      (node (ref "CON2") (pin "A8") (pinfunction "SBU1(A8)_A8") (pintype "passive"))
    )
    (net (code "68") (name "unconnected-(CON2-SBU2(B8)-PadB8)") (class "Default")
      (node (ref "CON2") (pin "B8") (pinfunction "SBU2(B8)_B8") (pintype "passive"))
    )
    (net (code "69") (name "unconnected-(CON3-CC1(A5)-PadA5)") (class "Default")
      (node (ref "CON3") (pin "A5") (pinfunction "CC1(A5)_A5") (pintype "passive"))
    )
    (net (code "70") (name "unconnected-(CON3-CC2(B5)-PadB5)") (class "Default")
      (node (ref "CON3") (pin "B5") (pinfunction "CC2(B5)_B5") (pintype "passive"))
    )
    (net (code "71") (name "unconnected-(CON3-SBU1(A8)-PadA8)") (class "Default")
      (node (ref "CON3") (pin "A8") (pinfunction "SBU1(A8)_A8") (pintype "passive"))
    )
    (net (code "72") (name "unconnected-(CON3-SBU2(B8)-PadB8)") (class "Default")
      (node (ref "CON3") (pin "B8") (pinfunction "SBU2(B8)_B8") (pintype "passive"))
    )
    (net (code "73") (name "unconnected-(U1B-PA1-Pad11)") (class "Default")
      (node (ref "U1") (pin "11") (pinfunction "PA1_11") (pintype "passive"))
    )
    (net (code "74") (name "unconnected-(U1B-PA4-Pad14)") (class "Default")
      (node (ref "U1") (pin "14") (pinfunction "PA4_14") (pintype "passive"))
    )
    (net (code "75") (name "unconnected-(U1B-PA6-Pad16)") (class "Default")
      (node (ref "U1") (pin "16") (pinfunction "PA6_16") (pintype "passive"))
    )
    (net (code "76") (name "unconnected-(U1B-PA7-Pad17)") (class "Default")
      (node (ref "U1") (pin "17") (pinfunction "PA7_17") (pintype "passive"))
    )
    (net (code "77") (name "unconnected-(U1B-PA8-Pad29)") (class "Default")
      (node (ref "U1") (pin "29") (pinfunction "PA8_29") (pintype "passive"))
    )
    (net (code "78") (name "unconnected-(U1B-PB1-Pad19)") (class "Default")
      (node (ref "U1") (pin "19") (pinfunction "PB1_19") (pintype "passive"))
    )
    (net (code "79") (name "unconnected-(U1B-PB5-Pad41)") (class "Default")
      (node (ref "U1") (pin "41") (pinfunction "PB5_41") (pintype "passive"))
    )
    (net (code "80") (name "unconnected-(U1B-PB7-Pad43)") (class "Default")
      (node (ref "U1") (pin "43") (pinfunction "PB7_43") (pintype "passive"))
    )
    (net (code "81") (name "unconnected-(U1B-PB8-Pad45)") (class "Default")
      (node (ref "U1") (pin "45") (pinfunction "PB8_45") (pintype "passive"))
    )
    (net (code "82") (name "unconnected-(U1B-PB9-Pad46)") (class "Default")
      (node (ref "U1") (pin "46") (pinfunction "PB9_46") (pintype "passive"))
    )
    (net (code "83") (name "unconnected-(U1B-PB10-Pad21)") (class "Default")
      (node (ref "U1") (pin "21") (pinfunction "PB10_21") (pintype "passive"))
    )
    (net (code "84") (name "unconnected-(U1B-PB11-Pad22)") (class "Default")
      (node (ref "U1") (pin "22") (pinfunction "PB11_22") (pintype "passive"))
    )
    (net (code "85") (name "unconnected-(U1B-PB15-Pad28)") (class "Default")
      (node (ref "U1") (pin "28") (pinfunction "PB15_28") (pintype "passive"))
    )
    (net (code "86") (name "unconnected-(U1B-PC15-Pad4)") (class "Default")
      (node (ref "U1") (pin "4") (pinfunction "PC15_4") (pintype "passive"))
    )
    (net (code "87") (name "unconnected-(U2-DM4-Pad1)") (class "Default")
      (node (ref "U2") (pin "1") (pinfunction "DM4_1") (pintype "passive"))
    )
    (net (code "88") (name "unconnected-(U2-DP4-Pad2)") (class "Default")
      (node (ref "U2") (pin "2") (pinfunction "DP4_2") (pintype "passive"))
    )
  )
)
